# chrono.net
KiCad netlist of a schematic drawn in EAGLE
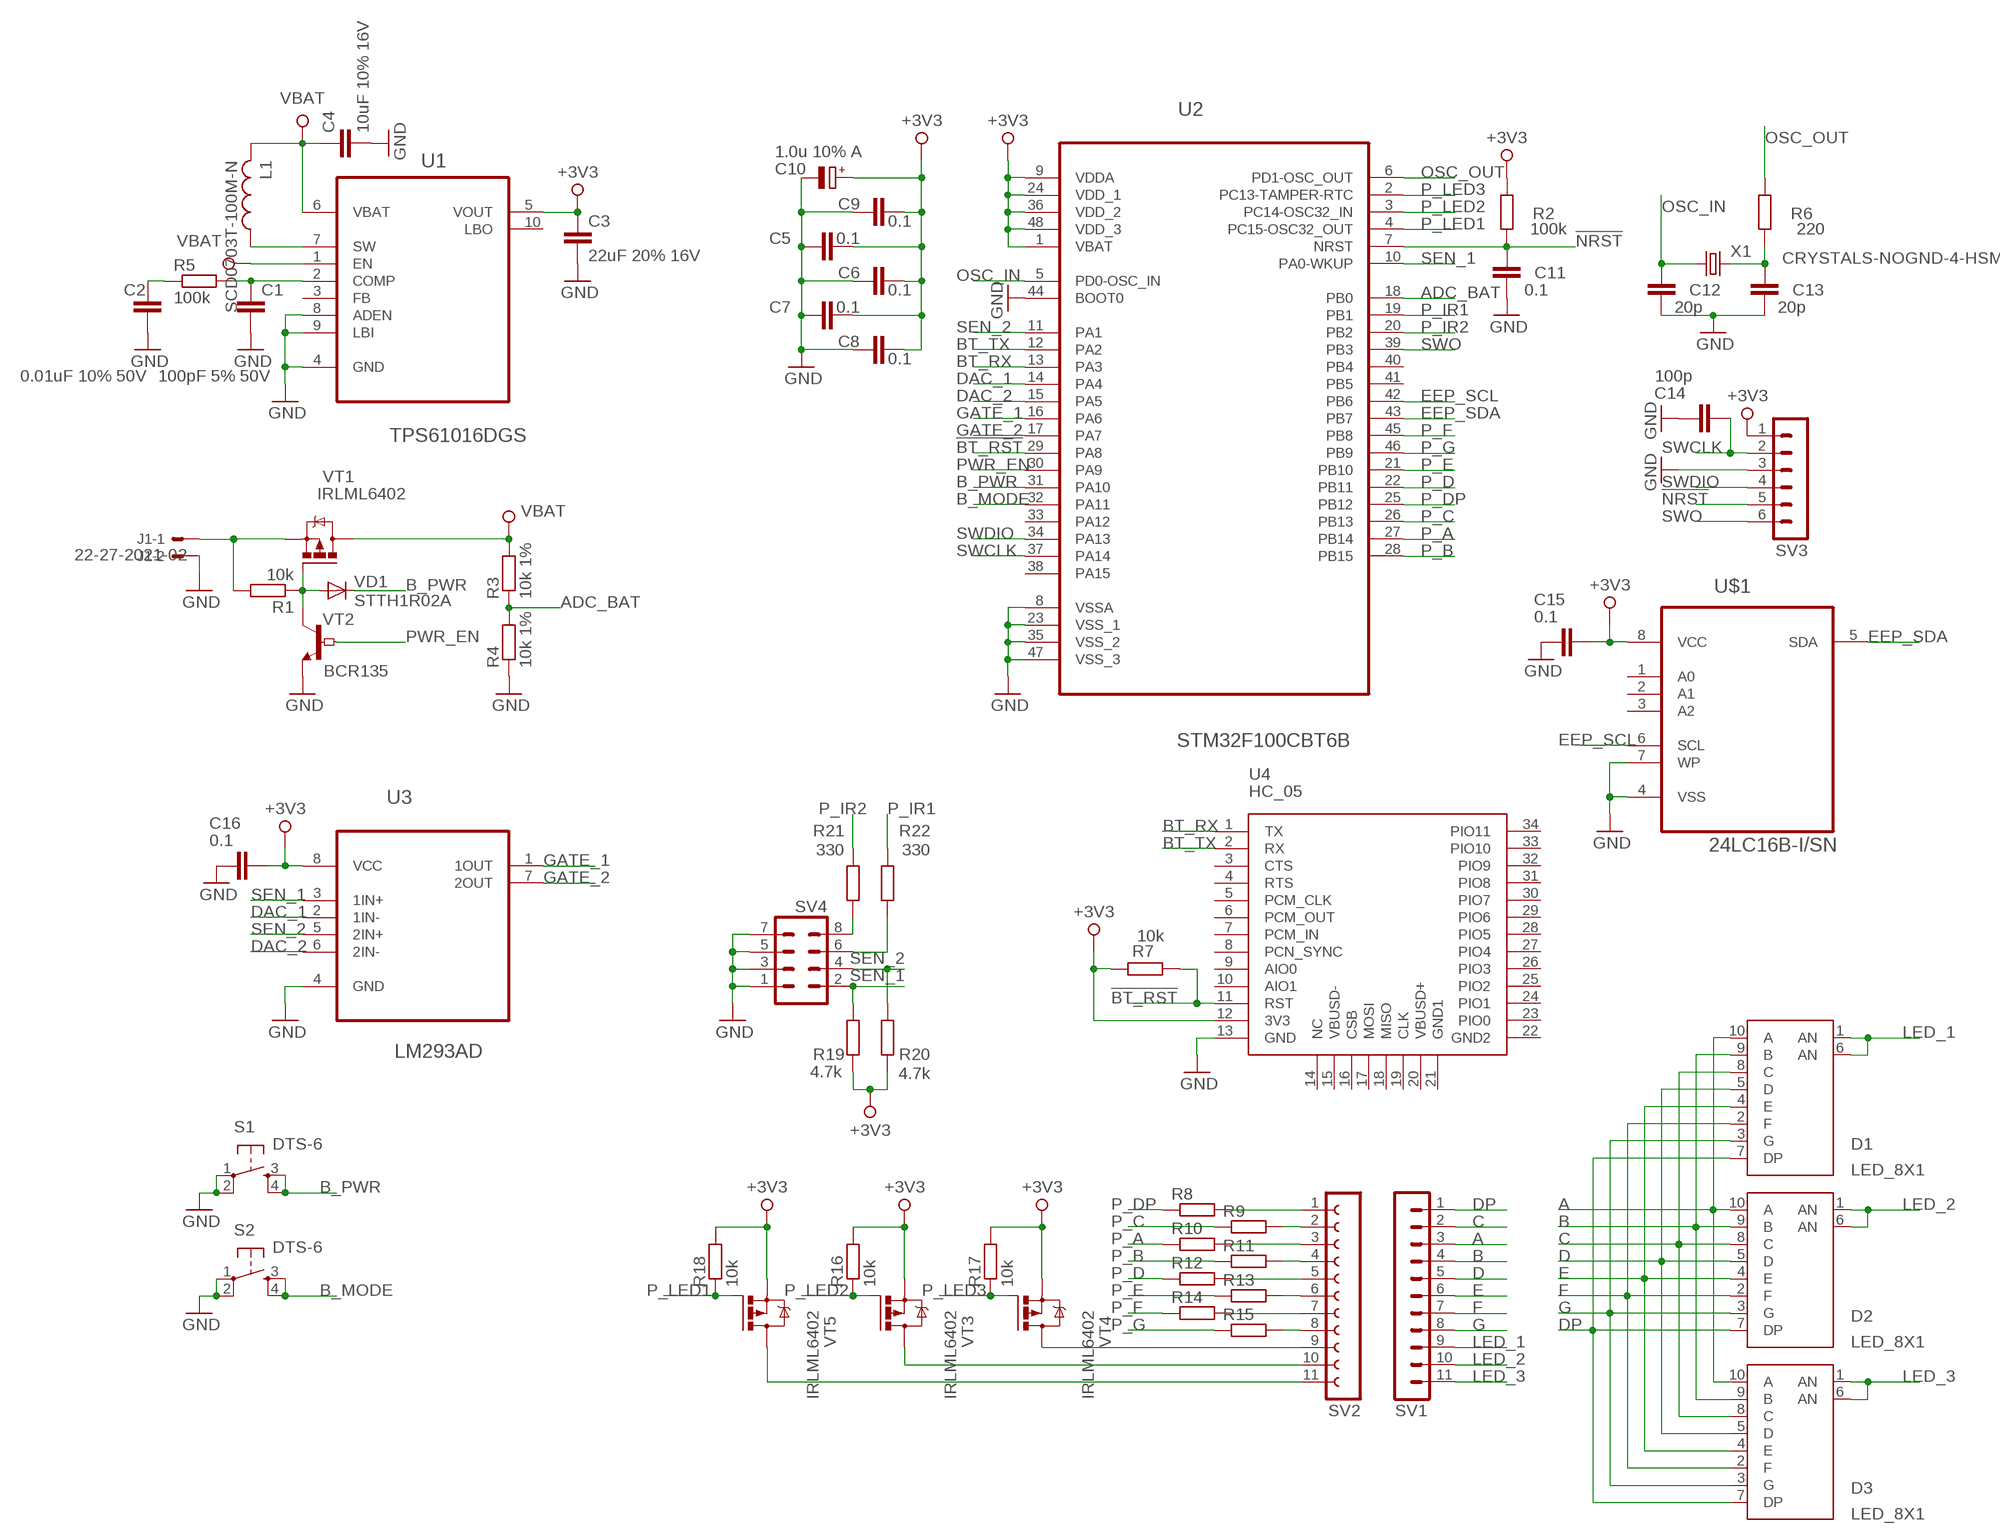
[diagram p0: schematic, sheet 1]

(export (version "E")
  (design (tool "Eeschema 10.0.6"))
  (components
    (comp (ref "C1")
      (value "100pF 5% 50V")
      (footprint "eagle-import:C0805")
      (libsource (lib "eagle-import") (part "C-EUC0805"))
    )
    (comp (ref "C2")
      (value "0.01uF 10% 50V")
      (footprint "eagle-import:C0805")
      (libsource (lib "eagle-import") (part "C-EUC0805"))
    )
    (comp (ref "C3")
      (value "22uF 20% 16V")
      (footprint "eagle-import:C1206")
      (libsource (lib "eagle-import") (part "C-EUC1206"))
    )
    (comp (ref "C4")
      (value "10uF 10% 16V")
      (footprint "eagle-import:C0805")
      (libsource (lib "eagle-import") (part "C-EUC0805"))
    )
    (comp (ref "C5")
      (value "0.1")
      (footprint "eagle-import:C0603")
      (libsource (lib "eagle-import") (part "C-EUC0603"))
    )
    (comp (ref "C6")
      (value "0.1")
      (footprint "eagle-import:C0603")
      (libsource (lib "eagle-import") (part "C-EUC0603"))
    )
    (comp (ref "C7")
      (value "0.1")
      (footprint "eagle-import:C0603")
      (libsource (lib "eagle-import") (part "C-EUC0603"))
    )
    (comp (ref "C8")
      (value "0.1")
      (footprint "eagle-import:C0603")
      (libsource (lib "eagle-import") (part "C-EUC0603"))
    )
    (comp (ref "C9")
      (value "0.1")
      (footprint "eagle-import:C0603")
      (libsource (lib "eagle-import") (part "C-EUC0603"))
    )
    (comp (ref "C10")
      (value "1.0u 10% A")
      (footprint "eagle-import:SMC_A")
      (libsource (lib "eagle-import") (part "CPOL-EUSMCA"))
    )
    (comp (ref "C11")
      (value "0.1")
      (footprint "eagle-import:C0603")
      (libsource (lib "eagle-import") (part "C-EUC0603"))
    )
    (comp (ref "C12")
      (value "20p")
      (footprint "eagle-import:C0603")
      (libsource (lib "eagle-import") (part "C-EUC0603"))
    )
    (comp (ref "C13")
      (value "20p")
      (footprint "eagle-import:C0603")
      (libsource (lib "eagle-import") (part "C-EUC0603"))
    )
    (comp (ref "C14")
      (value "100p")
      (footprint "eagle-import:C0603")
      (libsource (lib "eagle-import") (part "C-EUC0603"))
    )
    (comp (ref "C15")
      (value "0.1")
      (footprint "eagle-import:C0603")
      (libsource (lib "eagle-import") (part "C-EUC0603"))
    )
    (comp (ref "C16")
      (value "0.1")
      (footprint "eagle-import:C0603")
      (libsource (lib "eagle-import") (part "C-EUC0603"))
    )
    (comp (ref "D1")
      (value "LED_8X1")
      (footprint "eagle-import:LED_DIP10")
      (libsource (lib "eagle-import") (part "LED_8X1"))
    )
    (comp (ref "D2")
      (value "LED_8X1")
      (footprint "eagle-import:LED_DIP10")
      (libsource (lib "eagle-import") (part "LED_8X1"))
    )
    (comp (ref "D3")
      (value "LED_8X1")
      (footprint "eagle-import:LED_DIP10")
      (libsource (lib "eagle-import") (part "LED_8X1"))
    )
    (comp (ref "J1")
      (value "22-27-2021-02")
      (footprint "eagle-import:6410-02")
      (libsource (lib "eagle-import") (part "22-?-0227-2021"))
    )
    (comp (ref "L1")
      (value "SCD0703T-100M-N")
      (footprint "eagle-import:SCD0703")
      (libsource (lib "eagle-import") (part "L-US"))
    )
    (comp (ref "R1")
      (value "10k")
      (footprint "eagle-import:R0805")
      (libsource (lib "eagle-import") (part "R-EU_R0805"))
    )
    (comp (ref "R2")
      (value "100k")
      (footprint "eagle-import:R0603")
      (libsource (lib "eagle-import") (part "R-EU_R0603"))
    )
    (comp (ref "R3")
      (value "10k 1%")
      (footprint "eagle-import:R0603")
      (libsource (lib "eagle-import") (part "R-EU_R0603"))
    )
    (comp (ref "R4")
      (value "10k 1%")
      (footprint "eagle-import:R0603")
      (libsource (lib "eagle-import") (part "R-EU_R0603"))
    )
    (comp (ref "R5")
      (value "100k")
      (footprint "eagle-import:R0805")
      (libsource (lib "eagle-import") (part "R-EU_R0805"))
    )
    (comp (ref "R6")
      (value "220")
      (footprint "eagle-import:R0603")
      (libsource (lib "eagle-import") (part "R-EU_R0603"))
    )
    (comp (ref "R7")
      (value "10k")
      (footprint "eagle-import:R0603")
      (libsource (lib "eagle-import") (part "R-EU_R0603"))
    )
    (comp (ref "R8")
      (value "R-EU_R0603")
      (footprint "eagle-import:R0603")
      (libsource (lib "eagle-import") (part "R-EU_R0603"))
    )
    (comp (ref "R9")
      (value "R-EU_R0603")
      (footprint "eagle-import:R0603")
      (libsource (lib "eagle-import") (part "R-EU_R0603"))
    )
    (comp (ref "R10")
      (value "R-EU_R0603")
      (footprint "eagle-import:R0603")
      (libsource (lib "eagle-import") (part "R-EU_R0603"))
    )
    (comp (ref "R11")
      (value "R-EU_R0603")
      (footprint "eagle-import:R0603")
      (libsource (lib "eagle-import") (part "R-EU_R0603"))
    )
    (comp (ref "R12")
      (value "R-EU_R0603")
      (footprint "eagle-import:R0603")
      (libsource (lib "eagle-import") (part "R-EU_R0603"))
    )
    (comp (ref "R13")
      (value "R-EU_R0603")
      (footprint "eagle-import:R0603")
      (libsource (lib "eagle-import") (part "R-EU_R0603"))
    )
    (comp (ref "R14")
      (value "R-EU_R0603")
      (footprint "eagle-import:R0603")
      (libsource (lib "eagle-import") (part "R-EU_R0603"))
    )
    (comp (ref "R15")
      (value "R-EU_R0603")
      (footprint "eagle-import:R0603")
      (libsource (lib "eagle-import") (part "R-EU_R0603"))
    )
    (comp (ref "R16")
      (value "10k")
      (footprint "eagle-import:R0603")
      (libsource (lib "eagle-import") (part "R-EU_R0603"))
    )
    (comp (ref "R17")
      (value "10k")
      (footprint "eagle-import:R0603")
      (libsource (lib "eagle-import") (part "R-EU_R0603"))
    )
    (comp (ref "R18")
      (value "10k")
      (footprint "eagle-import:R0603")
      (libsource (lib "eagle-import") (part "R-EU_R0603"))
    )
    (comp (ref "R19")
      (value "4.7k")
      (footprint "eagle-import:R0603")
      (libsource (lib "eagle-import") (part "R-EU_R0603"))
    )
    (comp (ref "R20")
      (value "4.7k")
      (footprint "eagle-import:R0603")
      (libsource (lib "eagle-import") (part "R-EU_R0603"))
    )
    (comp (ref "R21")
      (value "330")
      (footprint "eagle-import:R0603")
      (libsource (lib "eagle-import") (part "R-EU_R0603"))
    )
    (comp (ref "R22")
      (value "330")
      (footprint "eagle-import:R0603")
      (libsource (lib "eagle-import") (part "R-EU_R0603"))
    )
    (comp (ref "S1")
      (value "DTS-6")
      (footprint "eagle-import:DTS-6")
      (libsource (lib "eagle-import") (part "DTS-6"))
    )
    (comp (ref "S2")
      (value "DTS-6")
      (footprint "eagle-import:DTS-6")
      (libsource (lib "eagle-import") (part "DTS-6"))
    )
    (comp (ref "SV1")
      (value "MA11-1W")
      (footprint "eagle-import:MA11-1W")
      (libsource (lib "eagle-import") (part "MA11-1W"))
    )
    (comp (ref "SV2")
      (value "FE11-1")
      (footprint "eagle-import:FE11")
      (libsource (lib "eagle-import") (part "FE11-1"))
    )
    (comp (ref "SV3")
      (value "MA06-1")
      (footprint "eagle-import:MA06-1")
      (libsource (lib "eagle-import") (part "MA06-1"))
    )
    (comp (ref "SV4")
      (value "MA04-2")
      (footprint "eagle-import:MA04-2")
      (libsource (lib "eagle-import") (part "MA04-2"))
    )
    (comp (ref "U$1")
      (value "24LC16B-I/SN")
      (footprint "eagle-import:SOIC127P600X175-8N")
      (libsource (lib "eagle-import") (part "24LC16B-I/SN"))
    )
    (comp (ref "U1")
      (value "TPS61016DGS")
      (footprint "eagle-import:SOP50P490X110-10N")
      (libsource (lib "eagle-import") (part "TPS61016DGS"))
    )
    (comp (ref "U2")
      (value "STM32F100CBT6B")
      (footprint "eagle-import:QFP50P900X900X160-48N")
      (libsource (lib "eagle-import") (part "STM32F100CBT6B"))
    )
    (comp (ref "U3")
      (value "LM293AD")
      (footprint "eagle-import:SOIC127P600X175-8N")
      (libsource (lib "eagle-import") (part "LM293AD"))
    )
    (comp (ref "U4")
      (value "HC_05")
      (footprint "eagle-import:BLUETOOTH_SMD")
      (libsource (lib "eagle-import") (part "HC_05"))
    )
    (comp (ref "VD1")
      (value "STTH1R02A")
      (footprint "eagle-import:SMA")
      (libsource (lib "eagle-import") (part "VD-SMA"))
    )
    (comp (ref "VT1")
      (value "IRLML6402")
      (footprint "eagle-import:MICRO3")
      (libsource (lib "eagle-import") (part "IRLML6402"))
    )
    (comp (ref "VT2")
      (value "BCR135")
      (footprint "eagle-import:SOT23-BEC")
      (libsource (lib "eagle-import") (part "VT_NPN_DIGITAL"))
    )
    (comp (ref "VT3")
      (value "IRLML6402")
      (footprint "eagle-import:MICRO3")
      (libsource (lib "eagle-import") (part "IRLML6402"))
    )
    (comp (ref "VT4")
      (value "IRLML6402")
      (footprint "eagle-import:MICRO3")
      (libsource (lib "eagle-import") (part "IRLML6402"))
    )
    (comp (ref "VT5")
      (value "IRLML6402")
      (footprint "eagle-import:MICRO3")
      (libsource (lib "eagle-import") (part "IRLML6402"))
    )
    (comp (ref "X1")
      (value "CRYSTALS-NOGND-4-HSMX")
      (footprint "eagle-import:HC49-4-HSMX")
      (libsource (lib "eagle-import") (part "CRYSTALS-NOGND-4-HSMX"))
    )
  )
  (nets
    (net (code "1") (name "+3V3") (class "Default")
      (node (ref "C10") (pin "+") (pinfunction "+_+") (pintype "passive"))
      (node (ref "C15") (pin "2") (pinfunction "2_2") (pintype "passive"))
      (node (ref "C16") (pin "2") (pinfunction "2_2") (pintype "passive"))
      (node (ref "C3") (pin "1") (pinfunction "1_1") (pintype "passive"))
      (node (ref "C5") (pin "2") (pinfunction "2_2") (pintype "passive"))
      (node (ref "C6") (pin "2") (pinfunction "2_2") (pintype "passive"))
      (node (ref "C7") (pin "2") (pinfunction "2_2") (pintype "passive"))
      (node (ref "C8") (pin "2") (pinfunction "2_2") (pintype "passive"))
      (node (ref "C9") (pin "1") (pinfunction "1_1") (pintype "passive"))
      (node (ref "R16") (pin "2") (pinfunction "2_2") (pintype "passive"))
      (node (ref "R17") (pin "2") (pinfunction "2_2") (pintype "passive"))
      (node (ref "R18") (pin "2") (pinfunction "2_2") (pintype "passive"))
      (node (ref "R19") (pin "1") (pinfunction "1_1") (pintype "passive"))
      (node (ref "R2") (pin "1") (pinfunction "1_1") (pintype "passive"))
      (node (ref "R20") (pin "1") (pinfunction "1_1") (pintype "passive"))
      (node (ref "R7") (pin "1") (pinfunction "1_1") (pintype "passive"))
      (node (ref "SV3") (pin "1") (pinfunction "1_1") (pintype "passive"))
      (node (ref "U$1") (pin "8") (pinfunction "VCC_8") (pintype "power_in"))
      (node (ref "U1") (pin "5") (pinfunction "VOUT_5") (pintype "output"))
      (node (ref "U2") (pin "1") (pinfunction "VBAT_1") (pintype "power_in"))
      (node (ref "U2") (pin "24") (pinfunction "VDD_1_24") (pintype "power_in"))
      (node (ref "U2") (pin "36") (pinfunction "VDD_2_36") (pintype "power_in"))
      (node (ref "U2") (pin "48") (pinfunction "VDD_3_48") (pintype "power_in"))
      (node (ref "U2") (pin "9") (pinfunction "VDDA_9") (pintype "power_in"))
      (node (ref "U3") (pin "8") (pinfunction "VCC_8") (pintype "power_in"))
      (node (ref "U4") (pin "12") (pinfunction "3V3_12") (pintype "bidirectional"))
      (node (ref "VT3") (pin "2") (pinfunction "S_2") (pintype "passive"))
      (node (ref "VT4") (pin "2") (pinfunction "S_2") (pintype "passive"))
      (node (ref "VT5") (pin "2") (pinfunction "S_2") (pintype "passive"))
    )
    (net (code "2") (name "/A") (class "Default")
      (node (ref "D1") (pin "10") (pinfunction "A_10") (pintype "bidirectional"))
      (node (ref "D2") (pin "10") (pinfunction "A_10") (pintype "bidirectional"))
      (node (ref "D3") (pin "10") (pinfunction "A_10") (pintype "bidirectional"))
      (node (ref "SV1") (pin "3") (pinfunction "3_3") (pintype "passive"))
    )
    (net (code "3") (name "/ADC_BAT") (class "Default")
      (node (ref "R3") (pin "1") (pinfunction "1_1") (pintype "passive"))
      (node (ref "R4") (pin "2") (pinfunction "2_2") (pintype "passive"))
      (node (ref "U2") (pin "18") (pinfunction "PB0_18") (pintype "bidirectional"))
    )
    (net (code "4") (name "/B") (class "Default")
      (node (ref "D1") (pin "9") (pinfunction "B_9") (pintype "bidirectional"))
      (node (ref "D2") (pin "9") (pinfunction "B_9") (pintype "bidirectional"))
      (node (ref "D3") (pin "9") (pinfunction "B_9") (pintype "bidirectional"))
      (node (ref "SV1") (pin "4") (pinfunction "4_4") (pintype "passive"))
    )
    (net (code "5") (name "/BT_RX") (class "Default")
      (node (ref "U2") (pin "13") (pinfunction "PA3_13") (pintype "bidirectional"))
      (node (ref "U4") (pin "1") (pinfunction "TX_1") (pintype "bidirectional"))
    )
    (net (code "6") (name "/BT_TX") (class "Default")
      (node (ref "U2") (pin "12") (pinfunction "PA2_12") (pintype "bidirectional"))
      (node (ref "U4") (pin "2") (pinfunction "RX_2") (pintype "bidirectional"))
    )
    (net (code "7") (name "/B_MODE") (class "Default")
      (node (ref "S2") (pin "3") (pinfunction "3_3") (pintype "passive"))
      (node (ref "S2") (pin "4") (pinfunction "4_4") (pintype "passive"))
      (node (ref "U2") (pin "32") (pinfunction "PA11_32") (pintype "bidirectional"))
    )
    (net (code "8") (name "/B_PWR") (class "Default")
      (node (ref "S1") (pin "3") (pinfunction "3_3") (pintype "passive"))
      (node (ref "S1") (pin "4") (pinfunction "4_4") (pintype "passive"))
      (node (ref "U2") (pin "31") (pinfunction "PA10_31") (pintype "bidirectional"))
      (node (ref "VD1") (pin "C") (pinfunction "C_C") (pintype "passive"))
    )
    (net (code "9") (name "/C") (class "Default")
      (node (ref "D1") (pin "8") (pinfunction "C_8") (pintype "bidirectional"))
      (node (ref "D2") (pin "8") (pinfunction "C_8") (pintype "bidirectional"))
      (node (ref "D3") (pin "8") (pinfunction "C_8") (pintype "bidirectional"))
      (node (ref "SV1") (pin "2") (pinfunction "2_2") (pintype "passive"))
    )
    (net (code "10") (name "/D") (class "Default")
      (node (ref "D1") (pin "5") (pinfunction "D_5") (pintype "bidirectional"))
      (node (ref "D2") (pin "5") (pinfunction "D_5") (pintype "bidirectional"))
      (node (ref "D3") (pin "5") (pinfunction "D_5") (pintype "bidirectional"))
      (node (ref "SV1") (pin "5") (pinfunction "5_5") (pintype "passive"))
    )
    (net (code "11") (name "/DAC_1") (class "Default")
      (node (ref "U2") (pin "14") (pinfunction "PA4_14") (pintype "bidirectional"))
      (node (ref "U3") (pin "2") (pinfunction "1IN-_2") (pintype "input"))
    )
    (net (code "12") (name "/DAC_2") (class "Default")
      (node (ref "U2") (pin "15") (pinfunction "PA5_15") (pintype "bidirectional"))
      (node (ref "U3") (pin "6") (pinfunction "2IN-_6") (pintype "input"))
    )
    (net (code "13") (name "/DP") (class "Default")
      (node (ref "D1") (pin "7") (pinfunction "DP_7") (pintype "bidirectional"))
      (node (ref "D2") (pin "7") (pinfunction "DP_7") (pintype "bidirectional"))
      (node (ref "D3") (pin "7") (pinfunction "DP_7") (pintype "bidirectional"))
      (node (ref "SV1") (pin "1") (pinfunction "1_1") (pintype "passive"))
    )
    (net (code "14") (name "/E") (class "Default")
      (node (ref "D1") (pin "4") (pinfunction "E_4") (pintype "bidirectional"))
      (node (ref "D2") (pin "4") (pinfunction "E_4") (pintype "bidirectional"))
      (node (ref "D3") (pin "4") (pinfunction "E_4") (pintype "bidirectional"))
      (node (ref "SV1") (pin "6") (pinfunction "6_6") (pintype "passive"))
    )
    (net (code "15") (name "/EEP_SCL") (class "Default")
      (node (ref "U$1") (pin "6") (pinfunction "SCL_6") (pintype "input"))
      (node (ref "U2") (pin "42") (pinfunction "PB6_42") (pintype "bidirectional"))
    )
    (net (code "16") (name "/EEP_SDA") (class "Default")
      (node (ref "U$1") (pin "5") (pinfunction "SDA_5") (pintype "bidirectional"))
      (node (ref "U2") (pin "43") (pinfunction "PB7_43") (pintype "bidirectional"))
    )
    (net (code "17") (name "/F") (class "Default")
      (node (ref "D1") (pin "2") (pinfunction "F_2") (pintype "bidirectional"))
      (node (ref "D2") (pin "2") (pinfunction "F_2") (pintype "bidirectional"))
      (node (ref "D3") (pin "2") (pinfunction "F_2") (pintype "bidirectional"))
      (node (ref "SV1") (pin "7") (pinfunction "7_7") (pintype "passive"))
    )
    (net (code "18") (name "/G") (class "Default")
      (node (ref "D1") (pin "3") (pinfunction "G_3") (pintype "bidirectional"))
      (node (ref "D2") (pin "3") (pinfunction "G_3") (pintype "bidirectional"))
      (node (ref "D3") (pin "3") (pinfunction "G_3") (pintype "bidirectional"))
      (node (ref "SV1") (pin "8") (pinfunction "8_8") (pintype "passive"))
    )
    (net (code "19") (name "/GATE_1") (class "Default")
      (node (ref "U2") (pin "16") (pinfunction "PA6_16") (pintype "bidirectional"))
      (node (ref "U3") (pin "1") (pinfunction "1OUT_1") (pintype "output"))
    )
    (net (code "20") (name "/GATE_2") (class "Default")
      (node (ref "U2") (pin "17") (pinfunction "PA7_17") (pintype "bidirectional"))
      (node (ref "U3") (pin "7") (pinfunction "2OUT_7") (pintype "output"))
    )
    (net (code "21") (name "/LED_1") (class "Default")
      (node (ref "D1") (pin "1") (pinfunction "AN_1") (pintype "bidirectional"))
      (node (ref "D1") (pin "6") (pinfunction "AN_6") (pintype "bidirectional"))
      (node (ref "SV1") (pin "9") (pinfunction "9_9") (pintype "passive"))
    )
    (net (code "22") (name "/LED_2") (class "Default")
      (node (ref "D2") (pin "1") (pinfunction "AN_1") (pintype "bidirectional"))
      (node (ref "D2") (pin "6") (pinfunction "AN_6") (pintype "bidirectional"))
      (node (ref "SV1") (pin "10") (pinfunction "10_10") (pintype "passive"))
    )
    (net (code "23") (name "/LED_3") (class "Default")
      (node (ref "D3") (pin "1") (pinfunction "AN_1") (pintype "bidirectional"))
      (node (ref "D3") (pin "6") (pinfunction "AN_6") (pintype "bidirectional"))
      (node (ref "SV1") (pin "11") (pinfunction "11_11") (pintype "passive"))
    )
    (net (code "24") (name "/OSC_IN") (class "Default")
      (node (ref "C12") (pin "1") (pinfunction "1_1") (pintype "passive"))
      (node (ref "U2") (pin "5") (pinfunction "PD0-OSC_IN_5") (pintype "input"))
      (node (ref "X1") (pin "1") (pinfunction "1_1") (pintype "passive"))
    )
    (net (code "25") (name "/OSC_OUT") (class "Default")
      (node (ref "R6") (pin "1") (pinfunction "1_1") (pintype "passive"))
      (node (ref "U2") (pin "6") (pinfunction "PD1-OSC_OUT_6") (pintype "output"))
    )
    (net (code "26") (name "/PWR_EN") (class "Default")
      (node (ref "U2") (pin "30") (pinfunction "PA9_30") (pintype "bidirectional"))
      (node (ref "VT2") (pin "B") (pinfunction "B_B") (pintype "passive"))
    )
    (net (code "27") (name "/P_A") (class "Default")
      (node (ref "R10") (pin "1") (pinfunction "1_1") (pintype "passive"))
      (node (ref "U2") (pin "27") (pinfunction "PB14_27") (pintype "bidirectional"))
    )
    (net (code "28") (name "/P_B") (class "Default")
      (node (ref "R11") (pin "1") (pinfunction "1_1") (pintype "passive"))
      (node (ref "U2") (pin "28") (pinfunction "PB15_28") (pintype "bidirectional"))
    )
    (net (code "29") (name "/P_C") (class "Default")
      (node (ref "R9") (pin "1") (pinfunction "1_1") (pintype "passive"))
      (node (ref "U2") (pin "26") (pinfunction "PB13_26") (pintype "bidirectional"))
    )
    (net (code "30") (name "/P_D") (class "Default")
      (node (ref "R12") (pin "1") (pinfunction "1_1") (pintype "passive"))
      (node (ref "U2") (pin "22") (pinfunction "PB11_22") (pintype "bidirectional"))
    )
    (net (code "31") (name "/P_DP") (class "Default")
      (node (ref "R8") (pin "1") (pinfunction "1_1") (pintype "passive"))
      (node (ref "U2") (pin "25") (pinfunction "PB12_25") (pintype "bidirectional"))
    )
    (net (code "32") (name "/P_E") (class "Default")
      (node (ref "R13") (pin "1") (pinfunction "1_1") (pintype "passive"))
      (node (ref "U2") (pin "21") (pinfunction "PB10_21") (pintype "bidirectional"))
    )
    (net (code "33") (name "/P_F") (class "Default")
      (node (ref "R14") (pin "1") (pinfunction "1_1") (pintype "passive"))
      (node (ref "U2") (pin "45") (pinfunction "PB8_45") (pintype "bidirectional"))
    )
    (net (code "34") (name "/P_G") (class "Default")
      (node (ref "R15") (pin "1") (pinfunction "1_1") (pintype "passive"))
      (node (ref "U2") (pin "46") (pinfunction "PB9_46") (pintype "bidirectional"))
    )
    (net (code "35") (name "/P_IR1") (class "Default")
      (node (ref "R22") (pin "2") (pinfunction "2_2") (pintype "passive"))
      (node (ref "U2") (pin "19") (pinfunction "PB1_19") (pintype "bidirectional"))
    )
    (net (code "36") (name "/P_IR2") (class "Default")
      (node (ref "R21") (pin "2") (pinfunction "2_2") (pintype "passive"))
      (node (ref "U2") (pin "20") (pinfunction "PB2_20") (pintype "bidirectional"))
    )
    (net (code "37") (name "/P_LED1") (class "Default")
      (node (ref "R18") (pin "1") (pinfunction "1_1") (pintype "passive"))
      (node (ref "U2") (pin "4") (pinfunction "PC15-OSC32_OUT_4") (pintype "bidirectional"))
      (node (ref "VT5") (pin "1") (pinfunction "G_1") (pintype "passive"))
    )
    (net (code "38") (name "/P_LED2") (class "Default")
      (node (ref "R16") (pin "1") (pinfunction "1_1") (pintype "passive"))
      (node (ref "U2") (pin "3") (pinfunction "PC14-OSC32_IN_3") (pintype "bidirectional"))
      (node (ref "VT3") (pin "1") (pinfunction "G_1") (pintype "passive"))
    )
    (net (code "39") (name "/P_LED3") (class "Default")
      (node (ref "R17") (pin "1") (pinfunction "1_1") (pintype "passive"))
      (node (ref "U2") (pin "2") (pinfunction "PC13-TAMPER-RTC_2") (pintype "bidirectional"))
      (node (ref "VT4") (pin "1") (pinfunction "G_1") (pintype "passive"))
    )
    (net (code "40") (name "/SEN_1") (class "Default")
      (node (ref "R19") (pin "2") (pinfunction "2_2") (pintype "passive"))
      (node (ref "SV4") (pin "2") (pinfunction "2_2") (pintype "passive"))
      (node (ref "U2") (pin "10") (pinfunction "PA0-WKUP_10") (pintype "bidirectional"))
      (node (ref "U3") (pin "3") (pinfunction "1IN+_3") (pintype "input"))
    )
    (net (code "41") (name "/SEN_2") (class "Default")
      (node (ref "R20") (pin "2") (pinfunction "2_2") (pintype "passive"))
      (node (ref "SV4") (pin "4") (pinfunction "4_4") (pintype "passive"))
      (node (ref "U2") (pin "11") (pinfunction "PA1_11") (pintype "bidirectional"))
      (node (ref "U3") (pin "5") (pinfunction "2IN+_5") (pintype "input"))
    )
    (net (code "42") (name "/SWCLK") (class "Default")
      (node (ref "C14") (pin "2") (pinfunction "2_2") (pintype "passive"))
      (node (ref "SV3") (pin "2") (pinfunction "2_2") (pintype "passive"))
      (node (ref "U2") (pin "37") (pinfunction "PA14_37") (pintype "bidirectional"))
    )
    (net (code "43") (name "/SWDIO") (class "Default")
      (node (ref "SV3") (pin "4") (pinfunction "4_4") (pintype "passive"))
      (node (ref "U2") (pin "34") (pinfunction "PA13_34") (pintype "bidirectional"))
    )
    (net (code "44") (name "/SWO") (class "Default")
      (node (ref "SV3") (pin "6") (pinfunction "6_6") (pintype "passive"))
      (node (ref "U2") (pin "39") (pinfunction "PB3_39") (pintype "bidirectional"))
    )
    (net (code "45") (name "/~{BT_RST}") (class "Default")
      (node (ref "R7") (pin "2") (pinfunction "2_2") (pintype "passive"))
      (node (ref "U2") (pin "29") (pinfunction "PA8_29") (pintype "bidirectional"))
      (node (ref "U4") (pin "11") (pinfunction "RST_11") (pintype "bidirectional"))
    )
    (net (code "46") (name "/~{NRST}") (class "Default")
      (node (ref "C11") (pin "1") (pinfunction "1_1") (pintype "passive"))
      (node (ref "R2") (pin "2") (pinfunction "2_2") (pintype "passive"))
      (node (ref "SV3") (pin "5") (pinfunction "5_5") (pintype "passive"))
      (node (ref "U2") (pin "7") (pinfunction "NRST_7") (pintype "bidirectional"))
    )
    (net (code "47") (name "GND") (class "Default")
      (node (ref "C1") (pin "2") (pinfunction "2_2") (pintype "passive"))
      (node (ref "C10") (pin "-") (pinfunction "-_-") (pintype "passive"))
      (node (ref "C11") (pin "2") (pinfunction "2_2") (pintype "passive"))
      (node (ref "C12") (pin "2") (pinfunction "2_2") (pintype "passive"))
      (node (ref "C13") (pin "2") (pinfunction "2_2") (pintype "passive"))
      (node (ref "C14") (pin "1") (pinfunction "1_1") (pintype "passive"))
      (node (ref "C15") (pin "1") (pinfunction "1_1") (pintype "passive"))
      (node (ref "C16") (pin "1") (pinfunction "1_1") (pintype "passive"))
      (node (ref "C2") (pin "2") (pinfunction "2_2") (pintype "passive"))
      (node (ref "C3") (pin "2") (pinfunction "2_2") (pintype "passive"))
      (node (ref "C4") (pin "2") (pinfunction "2_2") (pintype "passive"))
      (node (ref "C5") (pin "1") (pinfunction "1_1") (pintype "passive"))
      (node (ref "C6") (pin "1") (pinfunction "1_1") (pintype "passive"))
      (node (ref "C7") (pin "1") (pinfunction "1_1") (pintype "passive"))
      (node (ref "C8") (pin "1") (pinfunction "1_1") (pintype "passive"))
      (node (ref "C9") (pin "2") (pinfunction "2_2") (pintype "passive"))
      (node (ref "J1") (pin "2") (pinfunction "S_2") (pintype "passive"))
      (node (ref "R4") (pin "1") (pinfunction "1_1") (pintype "passive"))
      (node (ref "S1") (pin "1") (pinfunction "1_1") (pintype "passive"))
      (node (ref "S1") (pin "2") (pinfunction "2_2") (pintype "passive"))
      (node (ref "S2") (pin "1") (pinfunction "1_1") (pintype "passive"))
      (node (ref "S2") (pin "2") (pinfunction "2_2") (pintype "passive"))
      (node (ref "SV3") (pin "3") (pinfunction "3_3") (pintype "passive"))
      (node (ref "SV4") (pin "1") (pinfunction "1_1") (pintype "passive"))
      (node (ref "SV4") (pin "3") (pinfunction "3_3") (pintype "passive"))
      (node (ref "SV4") (pin "5") (pinfunction "5_5") (pintype "passive"))
      (node (ref "SV4") (pin "7") (pinfunction "7_7") (pintype "passive"))
      (node (ref "U$1") (pin "4") (pinfunction "VSS_4") (pintype "passive"))
      (node (ref "U$1") (pin "7") (pinfunction "WP_7") (pintype "input"))
      (node (ref "U1") (pin "4") (pinfunction "GND_4") (pintype "passive"))
      (node (ref "U1") (pin "8") (pinfunction "ADEN_8") (pintype "input"))
      (node (ref "U1") (pin "9") (pinfunction "LBI_9") (pintype "input"))
      (node (ref "U2") (pin "23") (pinfunction "VSS_1_23") (pintype "power_in"))
      (node (ref "U2") (pin "35") (pinfunction "VSS_2_35") (pintype "power_in"))
      (node (ref "U2") (pin "44") (pinfunction "BOOT0_44") (pintype "input"))
      (node (ref "U2") (pin "47") (pinfunction "VSS_3_47") (pintype "power_in"))
      (node (ref "U2") (pin "8") (pinfunction "VSSA_8") (pintype "power_in"))
      (node (ref "U3") (pin "4") (pinfunction "GND_4") (pintype "passive"))
      (node (ref "U4") (pin "13") (pinfunction "GND_13") (pintype "bidirectional"))
      (node (ref "VT2") (pin "E") (pinfunction "E_E") (pintype "passive"))
    )
    (net (code "48") (name "Net-(C2-Pad1)") (class "Default")
      (node (ref "C2") (pin "1") (pinfunction "1_1") (pintype "passive"))
      (node (ref "R5") (pin "1") (pinfunction "1_1") (pintype "passive"))
    )
    (net (code "49") (name "Net-(C13-Pad1)") (class "Default")
      (node (ref "C13") (pin "1") (pinfunction "1_1") (pintype "passive"))
      (node (ref "R6") (pin "2") (pinfunction "2_2") (pintype "passive"))
      (node (ref "X1") (pin "2") (pinfunction "2_2") (pintype "passive"))
    )
    (net (code "50") (name "Net-(J1A-S)") (class "Default")
      (node (ref "J1") (pin "1") (pinfunction "S_1") (pintype "passive"))
      (node (ref "R1") (pin "2") (pinfunction "2_2") (pintype "passive"))
      (node (ref "VT1") (pin "2") (pinfunction "S_2") (pintype "passive"))
    )
    (net (code "51") (name "Net-(L1-1)") (class "Default")
      (node (ref "L1") (pin "P$1") (pinfunction "1_P$1") (pintype "passive"))
      (node (ref "U1") (pin "7") (pinfunction "SW_7") (pintype "input"))
    )
    (net (code "52") (name "Net-(R8-Pad2)") (class "Default")
      (node (ref "R8") (pin "2") (pinfunction "2_2") (pintype "passive"))
      (node (ref "SV2") (pin "1") (pinfunction "1_1") (pintype "passive"))
    )
    (net (code "53") (name "Net-(R9-Pad2)") (class "Default")
      (node (ref "R9") (pin "2") (pinfunction "2_2") (pintype "passive"))
      (node (ref "SV2") (pin "2") (pinfunction "2_2") (pintype "passive"))
    )
    (net (code "54") (name "Net-(R10-Pad2)") (class "Default")
      (node (ref "R10") (pin "2") (pinfunction "2_2") (pintype "passive"))
      (node (ref "SV2") (pin "3") (pinfunction "3_3") (pintype "passive"))
    )
    (net (code "55") (name "Net-(R11-Pad2)") (class "Default")
      (node (ref "R11") (pin "2") (pinfunction "2_2") (pintype "passive"))
      (node (ref "SV2") (pin "4") (pinfunction "4_4") (pintype "passive"))
    )
    (net (code "56") (name "Net-(R12-Pad2)") (class "Default")
      (node (ref "R12") (pin "2") (pinfunction "2_2") (pintype "passive"))
      (node (ref "SV2") (pin "5") (pinfunction "5_5") (pintype "passive"))
    )
    (net (code "57") (name "Net-(R13-Pad2)") (class "Default")
      (node (ref "R13") (pin "2") (pinfunction "2_2") (pintype "passive"))
      (node (ref "SV2") (pin "6") (pinfunction "6_6") (pintype "passive"))
    )
    (net (code "58") (name "Net-(R14-Pad2)") (class "Default")
      (node (ref "R14") (pin "2") (pinfunction "2_2") (pintype "passive"))
      (node (ref "SV2") (pin "7") (pinfunction "7_7") (pintype "passive"))
    )
    (net (code "59") (name "Net-(R15-Pad2)") (class "Default")
      (node (ref "R15") (pin "2") (pinfunction "2_2") (pintype "passive"))
      (node (ref "SV2") (pin "8") (pinfunction "8_8") (pintype "passive"))
    )
    (net (code "60") (name "Net-(R21-Pad1)") (class "Default")
      (node (ref "R21") (pin "1") (pinfunction "1_1") (pintype "passive"))
      (node (ref "SV4") (pin "8") (pinfunction "8_8") (pintype "passive"))
    )
    (net (code "61") (name "Net-(R22-Pad1)") (class "Default")
      (node (ref "R22") (pin "1") (pinfunction "1_1") (pintype "passive"))
      (node (ref "SV4") (pin "6") (pinfunction "6_6") (pintype "passive"))
    )
    (net (code "62") (name "Net-(U1-COMP)") (class "Default")
      (node (ref "C1") (pin "1") (pinfunction "1_1") (pintype "passive"))
      (node (ref "R5") (pin "2") (pinfunction "2_2") (pintype "passive"))
      (node (ref "U1") (pin "2") (pinfunction "COMP_2") (pintype "input"))
    )
    (net (code "63") (name "Net-(VT1-G)") (class "Default")
      (node (ref "R1") (pin "1") (pinfunction "1_1") (pintype "passive"))
      (node (ref "VD1") (pin "A") (pinfunction "A_A") (pintype "passive"))
      (node (ref "VT1") (pin "1") (pinfunction "G_1") (pintype "passive"))
      (node (ref "VT2") (pin "C") (pinfunction "C_C") (pintype "passive"))
    )
    (net (code "64") (name "Net-(VT3-D)") (class "Default")
      (node (ref "SV2") (pin "10") (pinfunction "10_10") (pintype "passive"))
      (node (ref "VT3") (pin "3") (pinfunction "D_3") (pintype "passive"))
    )
    (net (code "65") (name "Net-(VT4-D)") (class "Default")
      (node (ref "SV2") (pin "9") (pinfunction "9_9") (pintype "passive"))
      (node (ref "VT4") (pin "3") (pinfunction "D_3") (pintype "passive"))
    )
    (net (code "66") (name "Net-(VT5-D)") (class "Default")
      (node (ref "SV2") (pin "11") (pinfunction "11_11") (pintype "passive"))
      (node (ref "VT5") (pin "3") (pinfunction "D_3") (pintype "passive"))
    )
    (net (code "67") (name "VBAT") (class "Default")
      (node (ref "C4") (pin "1") (pinfunction "1_1") (pintype "passive"))
      (node (ref "L1") (pin "P$2") (pinfunction "2_P$2") (pintype "passive"))
      (node (ref "R3") (pin "2") (pinfunction "2_2") (pintype "passive"))
      (node (ref "U1") (pin "1") (pinfunction "EN_1") (pintype "input"))
      (node (ref "U1") (pin "6") (pinfunction "VBAT_6") (pintype "power_in"))
      (node (ref "VT1") (pin "3") (pinfunction "D_3") (pintype "passive"))
    )
    (net (code "68") (name "unconnected-(U$1-A0-Pad1)") (class "Default")
      (node (ref "U$1") (pin "1") (pinfunction "A0_1") (pintype "input"))
    )
    (net (code "69") (name "unconnected-(U$1-A1-Pad2)") (class "Default")
      (node (ref "U$1") (pin "2") (pinfunction "A1_2") (pintype "input"))
    )
    (net (code "70") (name "unconnected-(U$1-A2-Pad3)") (class "Default")
      (node (ref "U$1") (pin "3") (pinfunction "A2_3") (pintype "input"))
    )
    (net (code "71") (name "unconnected-(U1-FB-Pad3)") (class "Default")
      (node (ref "U1") (pin "3") (pinfunction "FB_3") (pintype "input"))
    )
    (net (code "72") (name "unconnected-(U1-LBO-Pad10)") (class "Default")
      (node (ref "U1") (pin "10") (pinfunction "LBO_10") (pintype "output"))
    )
    (net (code "73") (name "unconnected-(U2-PA12-Pad33)") (class "Default")
      (node (ref "U2") (pin "33") (pinfunction "PA12_33") (pintype "bidirectional"))
    )
    (net (code "74") (name "unconnected-(U2-PA15-Pad38)") (class "Default")
      (node (ref "U2") (pin "38") (pinfunction "PA15_38") (pintype "bidirectional"))
    )
    (net (code "75") (name "unconnected-(U2-PB4-Pad40)") (class "Default")
      (node (ref "U2") (pin "40") (pinfunction "PB4_40") (pintype "bidirectional"))
    )
    (net (code "76") (name "unconnected-(U2-PB5-Pad41)") (class "Default")
      (node (ref "U2") (pin "41") (pinfunction "PB5_41") (pintype "bidirectional"))
    )
    (net (code "77") (name "unconnected-(U4-AIO0-Pad9)") (class "Default")
      (node (ref "U4") (pin "9") (pinfunction "AIO0_9") (pintype "bidirectional"))
    )
    (net (code "78") (name "unconnected-(U4-AIO1-Pad10)") (class "Default")
      (node (ref "U4") (pin "10") (pinfunction "AIO1_10") (pintype "bidirectional"))
    )
    (net (code "79") (name "unconnected-(U4-CLK-Pad19)") (class "Default")
      (node (ref "U4") (pin "19") (pinfunction "CLK_19") (pintype "bidirectional"))
    )
    (net (code "80") (name "unconnected-(U4-CSB-Pad16)") (class "Default")
      (node (ref "U4") (pin "16") (pinfunction "CSB_16") (pintype "bidirectional"))
    )
    (net (code "81") (name "unconnected-(U4-CTS-Pad3)") (class "Default")
      (node (ref "U4") (pin "3") (pinfunction "CTS_3") (pintype "bidirectional"))
    )
    (net (code "82") (name "unconnected-(U4-GND1-Pad21)") (class "Default")
      (node (ref "U4") (pin "21") (pinfunction "GND1_21") (pintype "bidirectional"))
    )
    (net (code "83") (name "unconnected-(U4-GND2-Pad22)") (class "Default")
      (node (ref "U4") (pin "22") (pinfunction "GND2_22") (pintype "bidirectional"))
    )
    (net (code "84") (name "unconnected-(U4-MISO-Pad18)") (class "Default")
      (node (ref "U4") (pin "18") (pinfunction "MISO_18") (pintype "bidirectional"))
    )
    (net (code "85") (name "unconnected-(U4-MOSI-Pad17)") (class "Default")
      (node (ref "U4") (pin "17") (pinfunction "MOSI_17") (pintype "bidirectional"))
    )
    (net (code "86") (name "unconnected-(U4-NC-Pad14)") (class "Default")
      (node (ref "U4") (pin "14") (pinfunction "NC_14") (pintype "bidirectional"))
    )
    (net (code "87") (name "unconnected-(U4-PCM_CLK-Pad5)") (class "Default")
      (node (ref "U4") (pin "5") (pinfunction "PCM_CLK_5") (pintype "bidirectional"))
    )
    (net (code "88") (name "unconnected-(U4-PCM_IN-Pad7)") (class "Default")
      (node (ref "U4") (pin "7") (pinfunction "PCM_IN_7") (pintype "bidirectional"))
    )
    (net (code "89") (name "unconnected-(U4-PCM_OUT-Pad6)") (class "Default")
      (node (ref "U4") (pin "6") (pinfunction "PCM_OUT_6") (pintype "bidirectional"))
    )
    (net (code "90") (name "unconnected-(U4-PCN_SYNC-Pad8)") (class "Default")
      (node (ref "U4") (pin "8") (pinfunction "PCN_SYNC_8") (pintype "bidirectional"))
    )
    (net (code "91") (name "unconnected-(U4-PIO0-Pad23)") (class "Default")
      (node (ref "U4") (pin "23") (pinfunction "PIO0_23") (pintype "bidirectional"))
    )
    (net (code "92") (name "unconnected-(U4-PIO1-Pad24)") (class "Default")
      (node (ref "U4") (pin "24") (pinfunction "PIO1_24") (pintype "bidirectional"))
    )
    (net (code "93") (name "unconnected-(U4-PIO2-Pad25)") (class "Default")
      (node (ref "U4") (pin "25") (pinfunction "PIO2_25") (pintype "bidirectional"))
    )
    (net (code "94") (name "unconnected-(U4-PIO3-Pad26)") (class "Default")
      (node (ref "U4") (pin "26") (pinfunction "PIO3_26") (pintype "bidirectional"))
    )
    (net (code "95") (name "unconnected-(U4-PIO4-Pad27)") (class "Default")
      (node (ref "U4") (pin "27") (pinfunction "PIO4_27") (pintype "bidirectional"))
    )
    (net (code "96") (name "unconnected-(U4-PIO5-Pad28)") (class "Default")
      (node (ref "U4") (pin "28") (pinfunction "PIO5_28") (pintype "bidirectional"))
    )
    (net (code "97") (name "unconnected-(U4-PIO6-Pad29)") (class "Default")
      (node (ref "U4") (pin "29") (pinfunction "PIO6_29") (pintype "bidirectional"))
    )
    (net (code "98") (name "unconnected-(U4-PIO7-Pad30)") (class "Default")
      (node (ref "U4") (pin "30") (pinfunction "PIO7_30") (pintype "bidirectional"))
    )
    (net (code "99") (name "unconnected-(U4-PIO8-Pad31)") (class "Default")
      (node (ref "U4") (pin "31") (pinfunction "PIO8_31") (pintype "bidirectional"))
    )
    (net (code "100") (name "unconnected-(U4-PIO9-Pad32)") (class "Default")
      (node (ref "U4") (pin "32") (pinfunction "PIO9_32") (pintype "bidirectional"))
    )
    (net (code "101") (name "unconnected-(U4-PIO10-Pad33)") (class "Default")
      (node (ref "U4") (pin "33") (pinfunction "PIO10_33") (pintype "bidirectional"))
    )
    (net (code "102") (name "unconnected-(U4-PIO11-Pad34)") (class "Default")
      (node (ref "U4") (pin "34") (pinfunction "PIO11_34") (pintype "bidirectional"))
    )
    (net (code "103") (name "unconnected-(U4-RTS-Pad4)") (class "Default")
      (node (ref "U4") (pin "4") (pinfunction "RTS_4") (pintype "bidirectional"))
    )
    (net (code "104") (name "unconnected-(U4-VBUSD+-Pad20)") (class "Default")
      (node (ref "U4") (pin "20") (pinfunction "VBUSD+_20") (pintype "bidirectional"))
    )
    (net (code "105") (name "unconnected-(U4-VBUSD--Pad15)") (class "Default")
      (node (ref "U4") (pin "15") (pinfunction "VBUSD-_15") (pintype "bidirectional"))
    )
  )
)
